# transimpedance_amp_simple.net
KiCad netlist of a schematic drawn in EAGLE
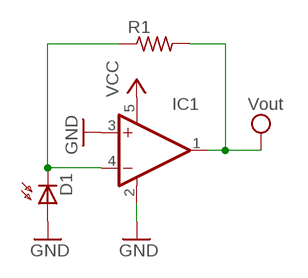
[diagram p0: schematic, sheet 1]

(export (version "E")
  (design (tool "Eeschema 10.0.6"))
  (components
    (comp (ref "D1")
      (value "BP104")
      (footprint "eagle-import:BP104")
      (fields (field (name "MF") "VISHAY/TELEFUNKEN"))
      (libsource (lib "eagle-import") (part "BP104"))
    )
    (comp (ref "IC1")
      (value "OPA336N")
      (footprint "eagle-import:SOT23-5")
      (fields (field (name "MPN") "OPA336NA"))
      (libsource (lib "eagle-import") (part "OPA336N"))
    )
    (comp (ref "R1")
      (value "R-US_0204/5")
      (footprint "eagle-import:0204_5")
      (libsource (lib "eagle-import") (part "R-US_0204/5"))
    )
  )
  (nets
    (net (code "1") (name "GND") (class "Default")
      (node (ref "D1") (pin "A") (pinfunction "A_A") (pintype "passive"))
      (node (ref "IC1") (pin "2") (pinfunction "V-_2") (pintype "power_in"))
      (node (ref "IC1") (pin "3") (pinfunction "+IN_3") (pintype "input"))
    )
    (net (code "2") (name "Net-(D1-C)") (class "Default")
      (node (ref "D1") (pin "K") (pinfunction "C_K") (pintype "passive"))
      (node (ref "IC1") (pin "4") (pinfunction "-IN_4") (pintype "input"))
      (node (ref "R1") (pin "1") (pinfunction "1_1") (pintype "passive"))
    )
    (net (code "3") (name "VCC") (class "Default")
      (node (ref "IC1") (pin "1") (pinfunction "OUT_1") (pintype "output"))
      (node (ref "IC1") (pin "5") (pinfunction "V+_5") (pintype "power_in"))
      (node (ref "R1") (pin "2") (pinfunction "2_2") (pintype "passive"))
    )
  )
)
